# design.net
KiCad netlist of a schematic drawn in Altium Designer
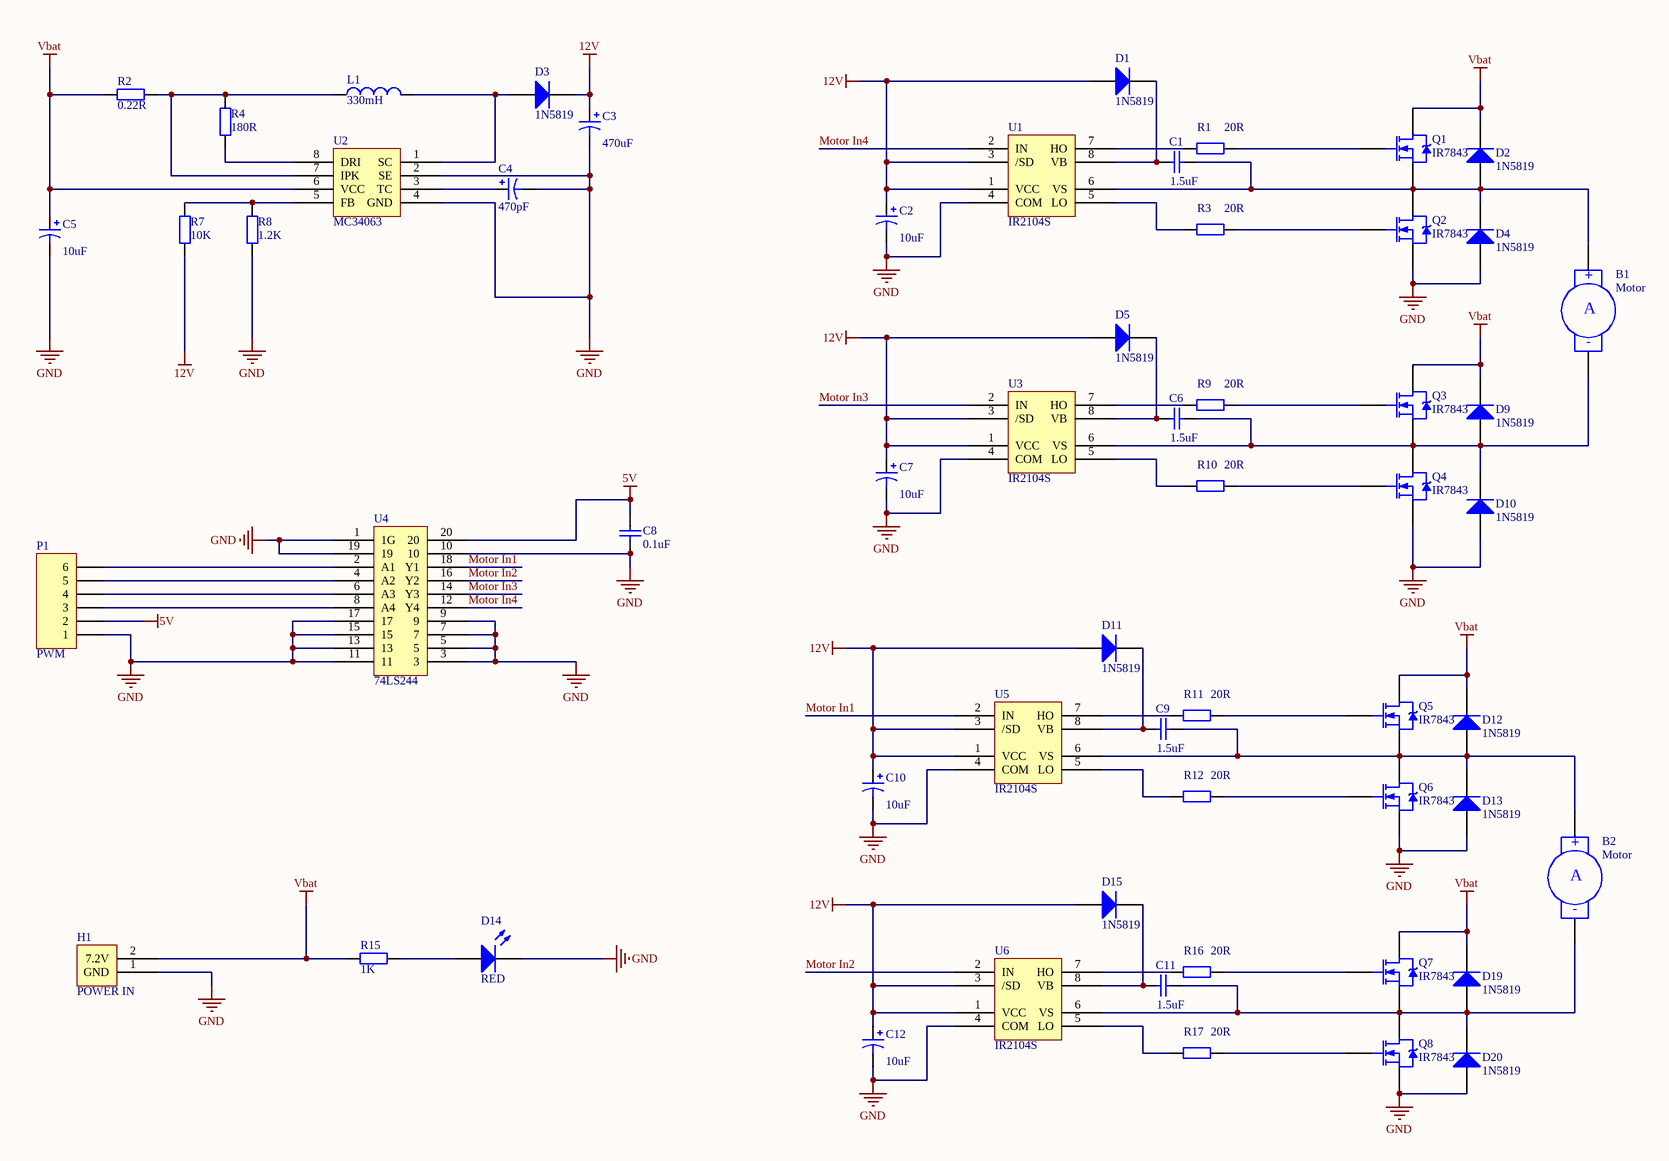
[diagram p0: 驱动原理图.SchDoc]

(export (version "E")
  (design (tool "Eeschema 10.0.6"))
  (components
    (comp (ref "B1")
      (value "Motor")
      (footprint "KF301-2P")
      (description "Servo Motor")
      (fields (field (name "PUBLISHER") "Altium Limited"))
      (libsource (lib "Miscellaneous Devices") (part "Motor Servo"))
    )
    (comp (ref "B2")
      (value "Motor")
      (footprint "KF301-2P")
      (description "Servo Motor")
      (fields (field (name "PUBLISHER") "Altium Limited"))
      (libsource (lib "Miscellaneous Devices") (part "Motor Servo"))
    )
    (comp (ref "C1")
      (value "1.5uF")
      (footprint "0805(2012)")
      (description "Capacitor")
      (fields (field (name "Comment") "Cap") (field (name "PUBLISHER") "Altium Limited"))
      (libsource (lib "Miscellaneous Devices") (part "Cap"))
    )
    (comp (ref "C2")
      (value "10uF")
      (footprint "SOD-323(0805)")
      (description "Polarized Capacitor (Radial)")
      (fields (field (name "Comment") "Cap Pol1") (field (name "PUBLISHER") "Altium Limited"))
      (libsource (lib "Miscellaneous Devices") (part "Cap Pol1"))
    )
    (comp (ref "C3")
      (value "470uF")
      (footprint "RB5-10.5")
      (description "Polarized Capacitor (Radial)")
      (fields (field (name "Comment") "Cap Pol1") (field (name "PUBLISHER") "Altium Limited"))
      (libsource (lib "Miscellaneous Devices") (part "Cap Pol1"))
    )
    (comp (ref "C4")
      (value "470pF")
      (footprint "SOD-323(0805)")
      (description "Polarized Capacitor (Radial)")
      (fields (field (name "Comment") "Cap Pol1") (field (name "PUBLISHER") "Altium Limited"))
      (libsource (lib "Miscellaneous Devices") (part "Cap Pol1"))
    )
    (comp (ref "C5")
      (value "10uF")
      (footprint "SOD-323(0805)")
      (description "Polarized Capacitor (Radial)")
      (fields (field (name "Comment") "Cap Pol1") (field (name "PUBLISHER") "Altium Limited"))
      (libsource (lib "Miscellaneous Devices") (part "Cap Pol1"))
    )
    (comp (ref "C6")
      (value "1.5uF")
      (footprint "0805(2012)")
      (description "Capacitor")
      (fields (field (name "Comment") "Cap") (field (name "PUBLISHER") "Altium Limited"))
      (libsource (lib "Miscellaneous Devices") (part "Cap"))
    )
    (comp (ref "C7")
      (value "10uF")
      (footprint "SOD-323(0805)")
      (description "Polarized Capacitor (Radial)")
      (fields (field (name "Comment") "Cap Pol1") (field (name "PUBLISHER") "Altium Limited"))
      (libsource (lib "Miscellaneous Devices") (part "Cap Pol1"))
    )
    (comp (ref "C8")
      (value "0.1uF")
      (footprint "0805(2012)")
      (description "Capacitor")
      (fields (field (name "Comment") "Cap") (field (name "PUBLISHER") "Altium Limited"))
      (libsource (lib "LY") (part "Cap"))
    )
    (comp (ref "C9")
      (value "1.5uF")
      (footprint "0805(2012)")
      (description "Capacitor")
      (fields (field (name "Comment") "Cap") (field (name "PUBLISHER") "Altium Limited"))
      (libsource (lib "Miscellaneous Devices") (part "Cap"))
    )
    (comp (ref "C10")
      (value "10uF")
      (footprint "SOD-323(0805)")
      (description "Polarized Capacitor (Radial)")
      (fields (field (name "Comment") "Cap Pol1") (field (name "PUBLISHER") "Altium Limited"))
      (libsource (lib "Miscellaneous Devices") (part "Cap Pol1"))
    )
    (comp (ref "C11")
      (value "1.5uF")
      (footprint "0805(2012)")
      (description "Capacitor")
      (fields (field (name "Comment") "Cap") (field (name "PUBLISHER") "Altium Limited"))
      (libsource (lib "Miscellaneous Devices") (part "Cap"))
    )
    (comp (ref "C12")
      (value "10uF")
      (footprint "SOD-323(0805)")
      (description "Polarized Capacitor (Radial)")
      (fields (field (name "Comment") "Cap Pol1") (field (name "PUBLISHER") "Altium Limited"))
      (libsource (lib "Miscellaneous Devices") (part "Cap Pol1"))
    )
    (comp (ref "D1")
      (value "1N5819")
      (footprint "0805(2012)")
      (description "Silicon Epitaxial Planar Diode for Various Detector, Modulator, Demodulator")
      (fields (field (name "PUBLISHER") "Altium Limited"))
      (libsource (lib "Renesas Diode") (part "1N4148"))
    )
    (comp (ref "D2")
      (value "1N5819")
      (footprint "0805(2012)")
      (description "Silicon Epitaxial Planar Diode for Various Detector, Modulator, Demodulator")
      (fields (field (name "PUBLISHER") "Altium Limited"))
      (libsource (lib "Renesas Diode") (part "1N4148"))
    )
    (comp (ref "D3")
      (value "1N5819")
      (footprint "0805(2012)")
      (description "Silicon Epitaxial Planar Diode for Various Detector, Modulator, Demodulator")
      (fields (field (name "PUBLISHER") "Altium Limited"))
      (libsource (lib "Renesas Diode") (part "1N4148"))
    )
    (comp (ref "D4")
      (value "1N5819")
      (footprint "0805(2012)")
      (description "Silicon Epitaxial Planar Diode for Various Detector, Modulator, Demodulator")
      (fields (field (name "PUBLISHER") "Altium Limited"))
      (libsource (lib "Renesas Diode") (part "1N4148"))
    )
    (comp (ref "D5")
      (value "1N5819")
      (footprint "0805(2012)")
      (description "Silicon Epitaxial Planar Diode for Various Detector, Modulator, Demodulator")
      (fields (field (name "PUBLISHER") "Altium Limited"))
      (libsource (lib "Renesas Diode") (part "1N4148"))
    )
    (comp (ref "D9")
      (value "1N5819")
      (footprint "0805(2012)")
      (description "Silicon Epitaxial Planar Diode for Various Detector, Modulator, Demodulator")
      (fields (field (name "PUBLISHER") "Altium Limited"))
      (libsource (lib "Renesas Diode") (part "1N4148"))
    )
    (comp (ref "D10")
      (value "1N5819")
      (footprint "0805(2012)")
      (description "Silicon Epitaxial Planar Diode for Various Detector, Modulator, Demodulator")
      (fields (field (name "PUBLISHER") "Altium Limited"))
      (libsource (lib "Renesas Diode") (part "1N4148"))
    )
    (comp (ref "D11")
      (value "1N5819")
      (footprint "0805(2012)")
      (description "Silicon Epitaxial Planar Diode for Various Detector, Modulator, Demodulator")
      (fields (field (name "PUBLISHER") "Altium Limited"))
      (libsource (lib "Renesas Diode") (part "1N4148"))
    )
    (comp (ref "D12")
      (value "1N5819")
      (footprint "0805(2012)")
      (description "Silicon Epitaxial Planar Diode for Various Detector, Modulator, Demodulator")
      (fields (field (name "PUBLISHER") "Altium Limited"))
      (libsource (lib "Renesas Diode") (part "1N4148"))
    )
    (comp (ref "D13")
      (value "1N5819")
      (footprint "0805(2012)")
      (description "Silicon Epitaxial Planar Diode for Various Detector, Modulator, Demodulator")
      (fields (field (name "PUBLISHER") "Altium Limited"))
      (libsource (lib "Renesas Diode") (part "1N4148"))
    )
    (comp (ref "D14")
      (value "RED")
      (footprint "0805LED")
      (description "Typical RED, GREEN, YELLOW, AMBER GaAs LED")
      (fields (field (name "PUBLISHER") "Altium Limited"))
      (libsource (lib "LY") (part "LED2"))
    )
    (comp (ref "D15")
      (value "1N5819")
      (footprint "0805(2012)")
      (description "Silicon Epitaxial Planar Diode for Various Detector, Modulator, Demodulator")
      (fields (field (name "PUBLISHER") "Altium Limited"))
      (libsource (lib "Renesas Diode") (part "1N4148"))
    )
    (comp (ref "D19")
      (value "1N5819")
      (footprint "0805(2012)")
      (description "Silicon Epitaxial Planar Diode for Various Detector, Modulator, Demodulator")
      (fields (field (name "PUBLISHER") "Altium Limited"))
      (libsource (lib "Renesas Diode") (part "1N4148"))
    )
    (comp (ref "D20")
      (value "1N5819")
      (footprint "0805(2012)")
      (description "Silicon Epitaxial Planar Diode for Various Detector, Modulator, Demodulator")
      (fields (field (name "PUBLISHER") "Altium Limited"))
      (libsource (lib "Renesas Diode") (part "1N4148"))
    )
    (comp (ref "H1")
      (value "POWER IN")
      (footprint "KF301-2P")
      (libsource (lib "MOS motor") (part "POWER IN"))
    )
    (comp (ref "L1")
      (value "330mH")
      (footprint "电感10*12")
      (description "Inductor")
      (fields (field (name "PUBLISHER") "Altium Limited"))
      (libsource (lib "Miscellaneous Devices") (part "Inductor"))
    )
    (comp (ref "P1")
      (value "PWM")
      (footprint "HDR1X6")
      (description "Header, 6-Pin")
      (fields (field (name "PUBLISHER") "Altium Limited"))
      (libsource (lib "Miscellaneous Connectors") (part "Header 6"))
    )
    (comp (ref "Q1")
      (value "IR7843")
      (footprint "LR7843")
      (description "N-Channel Power MOSFET")
      (fields (field (name "PUBLISHER") "Altium Limited"))
      (libsource (lib "PowerIn") (part "IR7843"))
    )
    (comp (ref "Q2")
      (value "IR7843")
      (footprint "LR7843")
      (description "N-Channel Power MOSFET")
      (fields (field (name "PUBLISHER") "Altium Limited"))
      (libsource (lib "PowerIn") (part "IR7843"))
    )
    (comp (ref "Q3")
      (value "IR7843")
      (footprint "LR7843")
      (description "N-Channel Power MOSFET")
      (fields (field (name "PUBLISHER") "Altium Limited"))
      (libsource (lib "PowerIn") (part "IR7843"))
    )
    (comp (ref "Q4")
      (value "IR7843")
      (footprint "LR7843")
      (description "N-Channel Power MOSFET")
      (fields (field (name "PUBLISHER") "Altium Limited"))
      (libsource (lib "PowerIn") (part "IR7843"))
    )
    (comp (ref "Q5")
      (value "IR7843")
      (footprint "LR7843")
      (description "N-Channel Power MOSFET")
      (fields (field (name "PUBLISHER") "Altium Limited"))
      (libsource (lib "PowerIn") (part "IR7843"))
    )
    (comp (ref "Q6")
      (value "IR7843")
      (footprint "LR7843")
      (description "N-Channel Power MOSFET")
      (fields (field (name "PUBLISHER") "Altium Limited"))
      (libsource (lib "PowerIn") (part "IR7843"))
    )
    (comp (ref "Q7")
      (value "IR7843")
      (footprint "LR7843")
      (description "N-Channel Power MOSFET")
      (fields (field (name "PUBLISHER") "Altium Limited"))
      (libsource (lib "PowerIn") (part "IR7843"))
    )
    (comp (ref "Q8")
      (value "IR7843")
      (footprint "LR7843")
      (description "N-Channel Power MOSFET")
      (fields (field (name "PUBLISHER") "Altium Limited"))
      (libsource (lib "PowerIn") (part "IR7843"))
    )
    (comp (ref "R1")
      (value "20R")
      (footprint "0805(2012)")
      (description "Resistor")
      (fields (field (name "Comment") "Res2") (field (name "PUBLISHER") "Altium Limited"))
      (libsource (lib "altium-import") (part "root_0_Res2_"))
    )
    (comp (ref "R2")
      (value "0.22R")
      (footprint "1206(3216)")
      (description "Resistor")
      (fields (field (name "Comment") "Res2") (field (name "PUBLISHER") "Altium Limited"))
      (libsource (lib "altium-import") (part "root_2_Res2_"))
    )
    (comp (ref "R3")
      (value "20R")
      (footprint "0805(2012)")
      (description "Resistor")
      (fields (field (name "Comment") "Res2") (field (name "PUBLISHER") "Altium Limited"))
      (libsource (lib "altium-import") (part "root_0_Res2_"))
    )
    (comp (ref "R4")
      (value "180R")
      (footprint "0805(2012)")
      (description "Resistor")
      (fields (field (name "Comment") "Res2") (field (name "PUBLISHER") "Altium Limited"))
      (libsource (lib "") (part "Res2_1"))
    )
    (comp (ref "R7")
      (value "10K")
      (footprint "0805(2012)")
      (description "Resistor")
      (fields (field (name "Comment") "Res2") (field (name "PUBLISHER") "Altium Limited"))
      (libsource (lib "") (part "Res2_1"))
    )
    (comp (ref "R8")
      (value "1.2K")
      (footprint "0805(2012)")
      (description "Resistor")
      (fields (field (name "Comment") "Res2") (field (name "PUBLISHER") "Altium Limited"))
      (libsource (lib "") (part "Res2_1"))
    )
    (comp (ref "R9")
      (value "20R")
      (footprint "0805(2012)")
      (description "Resistor")
      (fields (field (name "Comment") "Res2") (field (name "PUBLISHER") "Altium Limited"))
      (libsource (lib "altium-import") (part "root_0_Res2_"))
    )
    (comp (ref "R10")
      (value "20R")
      (footprint "0805(2012)")
      (description "Resistor")
      (fields (field (name "Comment") "Res2") (field (name "PUBLISHER") "Altium Limited"))
      (libsource (lib "altium-import") (part "root_0_Res2_"))
    )
    (comp (ref "R11")
      (value "20R")
      (footprint "0805(2012)")
      (description "Resistor")
      (fields (field (name "Comment") "Res2") (field (name "PUBLISHER") "Altium Limited"))
      (libsource (lib "altium-import") (part "root_0_Res2_"))
    )
    (comp (ref "R12")
      (value "20R")
      (footprint "0805(2012)")
      (description "Resistor")
      (fields (field (name "Comment") "Res2") (field (name "PUBLISHER") "Altium Limited"))
      (libsource (lib "altium-import") (part "root_0_Res2_"))
    )
    (comp (ref "R15")
      (value "1K")
      (footprint "0805(2012)")
      (description "Resistor")
      (fields (field (name "Comment") "Res2") (field (name "PUBLISHER") "Altium Limited"))
      (libsource (lib "LY") (part "Res2"))
    )
    (comp (ref "R16")
      (value "20R")
      (footprint "0805(2012)")
      (description "Resistor")
      (fields (field (name "Comment") "Res2") (field (name "PUBLISHER") "Altium Limited"))
      (libsource (lib "altium-import") (part "root_0_Res2_"))
    )
    (comp (ref "R17")
      (value "20R")
      (footprint "0805(2012)")
      (description "Resistor")
      (fields (field (name "Comment") "Res2") (field (name "PUBLISHER") "Altium Limited"))
      (libsource (lib "altium-import") (part "root_0_Res2_"))
    )
    (comp (ref "U1") (value "IR2104S") (footprint "IR2104S") (libsource (lib "LY") (part "IR2104S")))
    (comp (ref "U2") (value "MC34063") (footprint "MC34063") (libsource (lib "LY") (part "MC34063")))
    (comp (ref "U3") (value "IR2104S") (footprint "IR2104S") (libsource (lib "LY") (part "IR2104S")))
    (comp (ref "U4") (value "74LS244") (footprint "74ls244DA") (libsource (lib "LY") (part "74LS244")))
    (comp (ref "U5") (value "IR2104S") (footprint "IR2104S") (libsource (lib "LY") (part "IR2104S")))
    (comp (ref "U6") (value "IR2104S") (footprint "IR2104S") (libsource (lib "LY") (part "IR2104S")))
  )
  (nets
    (net (code "1") (name "/Motor In1") (class "Default")
      (node (ref "U4") (pin "18") (pinfunction "Y1_18") (pintype "passive"))
      (node (ref "U5") (pin "2") (pinfunction "IN_2") (pintype "passive"))
    )
    (net (code "2") (name "/Motor In2") (class "Default")
      (node (ref "U4") (pin "16") (pinfunction "Y2_16") (pintype "passive"))
      (node (ref "U6") (pin "2") (pinfunction "IN_2") (pintype "passive"))
    )
    (net (code "3") (name "/Motor In3") (class "Default")
      (node (ref "U3") (pin "2") (pinfunction "IN_2") (pintype "passive"))
      (node (ref "U4") (pin "14") (pinfunction "Y3_14") (pintype "passive"))
    )
    (net (code "4") (name "/Motor In4") (class "Default")
      (node (ref "U1") (pin "2") (pinfunction "IN_2") (pintype "passive"))
      (node (ref "U4") (pin "12") (pinfunction "Y4_12") (pintype "passive"))
    )
    (net (code "5") (name "5V") (class "Default")
      (node (ref "C8") (pin "2") (pinfunction "2_2") (pintype "passive"))
      (node (ref "P1") (pin "2") (pinfunction "2_2") (pintype "passive"))
      (node (ref "U4") (pin "20") (pinfunction "20_20") (pintype "passive"))
    )
    (net (code "6") (name "12V") (class "Default")
      (node (ref "C10") (pin "1") (pinfunction "1_1") (pintype "passive"))
      (node (ref "C12") (pin "1") (pinfunction "1_1") (pintype "passive"))
      (node (ref "C2") (pin "1") (pinfunction "1_1") (pintype "passive"))
      (node (ref "C3") (pin "1") (pinfunction "1_1") (pintype "passive"))
      (node (ref "C7") (pin "1") (pinfunction "1_1") (pintype "passive"))
      (node (ref "D1") (pin "2") (pinfunction "A_2") (pintype "passive"))
      (node (ref "D11") (pin "2") (pinfunction "A_2") (pintype "passive"))
      (node (ref "D15") (pin "2") (pinfunction "A_2") (pintype "passive"))
      (node (ref "D3") (pin "1") (pinfunction "K_1") (pintype "passive"))
      (node (ref "D5") (pin "2") (pinfunction "A_2") (pintype "passive"))
      (node (ref "R7") (pin "1") (pinfunction "1_1") (pintype "passive"))
      (node (ref "U1") (pin "1") (pinfunction "VCC_1") (pintype "passive"))
      (node (ref "U1") (pin "3") (pinfunction "/SD_3") (pintype "passive"))
      (node (ref "U3") (pin "1") (pinfunction "VCC_1") (pintype "passive"))
      (node (ref "U3") (pin "3") (pinfunction "/SD_3") (pintype "passive"))
      (node (ref "U5") (pin "1") (pinfunction "VCC_1") (pintype "passive"))
      (node (ref "U5") (pin "3") (pinfunction "/SD_3") (pintype "passive"))
      (node (ref "U6") (pin "1") (pinfunction "VCC_1") (pintype "passive"))
      (node (ref "U6") (pin "3") (pinfunction "/SD_3") (pintype "passive"))
    )
    (net (code "7") (name "GND") (class "Default")
      (node (ref "C10") (pin "2") (pinfunction "2_2") (pintype "passive"))
      (node (ref "C12") (pin "2") (pinfunction "2_2") (pintype "passive"))
      (node (ref "C2") (pin "2") (pinfunction "2_2") (pintype "passive"))
      (node (ref "C3") (pin "2") (pinfunction "2_2") (pintype "passive"))
      (node (ref "C4") (pin "2") (pinfunction "2_2") (pintype "passive"))
      (node (ref "C5") (pin "2") (pinfunction "2_2") (pintype "passive"))
      (node (ref "C7") (pin "2") (pinfunction "2_2") (pintype "passive"))
      (node (ref "C8") (pin "1") (pinfunction "1_1") (pintype "passive"))
      (node (ref "D10") (pin "2") (pinfunction "A_2") (pintype "passive"))
      (node (ref "D13") (pin "2") (pinfunction "A_2") (pintype "passive"))
      (node (ref "D14") (pin "2") (pinfunction "K_2") (pintype "passive"))
      (node (ref "D20") (pin "2") (pinfunction "A_2") (pintype "passive"))
      (node (ref "D4") (pin "2") (pinfunction "A_2") (pintype "passive"))
      (node (ref "H1") (pin "1") (pinfunction "GND_1") (pintype "passive"))
      (node (ref "P1") (pin "1") (pinfunction "1_1") (pintype "passive"))
      (node (ref "Q2") (pin "3") (pinfunction "S_3") (pintype "passive"))
      (node (ref "Q4") (pin "3") (pinfunction "S_3") (pintype "passive"))
      (node (ref "Q6") (pin "3") (pinfunction "S_3") (pintype "passive"))
      (node (ref "Q8") (pin "3") (pinfunction "S_3") (pintype "passive"))
      (node (ref "R8") (pin "1") (pinfunction "1_1") (pintype "passive"))
      (node (ref "U1") (pin "4") (pinfunction "COM_4") (pintype "passive"))
      (node (ref "U2") (pin "2") (pinfunction "SE_2") (pintype "passive"))
      (node (ref "U2") (pin "4") (pinfunction "GND_4") (pintype "passive"))
      (node (ref "U3") (pin "4") (pinfunction "COM_4") (pintype "passive"))
      (node (ref "U4") (pin "1") (pinfunction "1G_1") (pintype "passive"))
      (node (ref "U4") (pin "10") (pinfunction "10_10") (pintype "passive"))
      (node (ref "U4") (pin "11") (pinfunction "11_11") (pintype "passive"))
      (node (ref "U4") (pin "13") (pinfunction "13_13") (pintype "passive"))
      (node (ref "U4") (pin "15") (pinfunction "15_15") (pintype "passive"))
      (node (ref "U4") (pin "17") (pinfunction "17_17") (pintype "passive"))
      (node (ref "U4") (pin "19") (pinfunction "19_19") (pintype "passive"))
      (node (ref "U4") (pin "3") (pinfunction "3_3") (pintype "passive"))
      (node (ref "U4") (pin "5") (pinfunction "5_5") (pintype "passive"))
      (node (ref "U4") (pin "7") (pinfunction "7_7") (pintype "passive"))
      (node (ref "U4") (pin "9") (pinfunction "9_9") (pintype "passive"))
      (node (ref "U5") (pin "4") (pinfunction "COM_4") (pintype "passive"))
      (node (ref "U6") (pin "4") (pinfunction "COM_4") (pintype "passive"))
    )
    (net (code "8") (name "Net-(B1-+)") (class "Default")
      (node (ref "B1") (pin "1") (pinfunction "+_1") (pintype "passive"))
      (node (ref "C1") (pin "2") (pinfunction "2_2") (pintype "passive"))
      (node (ref "D2") (pin "2") (pinfunction "A_2") (pintype "passive"))
      (node (ref "D4") (pin "1") (pinfunction "K_1") (pintype "passive"))
      (node (ref "Q1") (pin "3") (pinfunction "S_3") (pintype "passive"))
      (node (ref "Q2") (pin "2") (pinfunction "D_2") (pintype "passive"))
      (node (ref "U1") (pin "6") (pinfunction "VS_6") (pintype "passive"))
    )
    (net (code "9") (name "Net-(B1--)") (class "Default")
      (node (ref "B1") (pin "2") (pinfunction "-_2") (pintype "passive"))
      (node (ref "C6") (pin "2") (pinfunction "2_2") (pintype "passive"))
      (node (ref "D10") (pin "1") (pinfunction "K_1") (pintype "passive"))
      (node (ref "D9") (pin "2") (pinfunction "A_2") (pintype "passive"))
      (node (ref "Q3") (pin "3") (pinfunction "S_3") (pintype "passive"))
      (node (ref "Q4") (pin "2") (pinfunction "D_2") (pintype "passive"))
      (node (ref "U3") (pin "6") (pinfunction "VS_6") (pintype "passive"))
    )
    (net (code "10") (name "Net-(B2-+)") (class "Default")
      (node (ref "B2") (pin "1") (pinfunction "+_1") (pintype "passive"))
      (node (ref "C9") (pin "2") (pinfunction "2_2") (pintype "passive"))
      (node (ref "D12") (pin "2") (pinfunction "A_2") (pintype "passive"))
      (node (ref "D13") (pin "1") (pinfunction "K_1") (pintype "passive"))
      (node (ref "Q5") (pin "3") (pinfunction "S_3") (pintype "passive"))
      (node (ref "Q6") (pin "2") (pinfunction "D_2") (pintype "passive"))
      (node (ref "U5") (pin "6") (pinfunction "VS_6") (pintype "passive"))
    )
    (net (code "11") (name "Net-(B2--)") (class "Default")
      (node (ref "B2") (pin "2") (pinfunction "-_2") (pintype "passive"))
      (node (ref "C11") (pin "2") (pinfunction "2_2") (pintype "passive"))
      (node (ref "D19") (pin "2") (pinfunction "A_2") (pintype "passive"))
      (node (ref "D20") (pin "1") (pinfunction "K_1") (pintype "passive"))
      (node (ref "Q7") (pin "3") (pinfunction "S_3") (pintype "passive"))
      (node (ref "Q8") (pin "2") (pinfunction "D_2") (pintype "passive"))
      (node (ref "U6") (pin "6") (pinfunction "VS_6") (pintype "passive"))
    )
    (net (code "12") (name "Net-(D1-K)") (class "Default")
      (node (ref "C1") (pin "1") (pinfunction "1_1") (pintype "passive"))
      (node (ref "D1") (pin "1") (pinfunction "K_1") (pintype "passive"))
      (node (ref "U1") (pin "8") (pinfunction "VB_8") (pintype "passive"))
    )
    (net (code "13") (name "Net-(D3-A)") (class "Default")
      (node (ref "D3") (pin "2") (pinfunction "A_2") (pintype "passive"))
      (node (ref "L1") (pin "2") (pinfunction "2_2") (pintype "passive"))
      (node (ref "U2") (pin "1") (pinfunction "SC_1") (pintype "passive"))
    )
    (net (code "14") (name "Net-(D5-K)") (class "Default")
      (node (ref "C6") (pin "1") (pinfunction "1_1") (pintype "passive"))
      (node (ref "D5") (pin "1") (pinfunction "K_1") (pintype "passive"))
      (node (ref "U3") (pin "8") (pinfunction "VB_8") (pintype "passive"))
    )
    (net (code "15") (name "Net-(D11-K)") (class "Default")
      (node (ref "C9") (pin "1") (pinfunction "1_1") (pintype "passive"))
      (node (ref "D11") (pin "1") (pinfunction "K_1") (pintype "passive"))
      (node (ref "U5") (pin "8") (pinfunction "VB_8") (pintype "passive"))
    )
    (net (code "16") (name "Net-(D14-A)") (class "Default")
      (node (ref "D14") (pin "1") (pinfunction "A_1") (pintype "passive"))
      (node (ref "R15") (pin "2") (pinfunction "2_2") (pintype "passive"))
    )
    (net (code "17") (name "Net-(D15-K)") (class "Default")
      (node (ref "C11") (pin "1") (pinfunction "1_1") (pintype "passive"))
      (node (ref "D15") (pin "1") (pinfunction "K_1") (pintype "passive"))
      (node (ref "U6") (pin "8") (pinfunction "VB_8") (pintype "passive"))
    )
    (net (code "18") (name "Net-(Q1-G)") (class "Default")
      (node (ref "Q1") (pin "1") (pinfunction "G_1") (pintype "passive"))
      (node (ref "R1") (pin "2") (pinfunction "2_2") (pintype "passive"))
    )
    (net (code "19") (name "Net-(Q2-G)") (class "Default")
      (node (ref "Q2") (pin "1") (pinfunction "G_1") (pintype "passive"))
      (node (ref "R3") (pin "2") (pinfunction "2_2") (pintype "passive"))
    )
    (net (code "20") (name "Net-(Q3-G)") (class "Default")
      (node (ref "Q3") (pin "1") (pinfunction "G_1") (pintype "passive"))
      (node (ref "R9") (pin "2") (pinfunction "2_2") (pintype "passive"))
    )
    (net (code "21") (name "Net-(Q4-G)") (class "Default")
      (node (ref "Q4") (pin "1") (pinfunction "G_1") (pintype "passive"))
      (node (ref "R10") (pin "2") (pinfunction "2_2") (pintype "passive"))
    )
    (net (code "22") (name "Net-(Q5-G)") (class "Default")
      (node (ref "Q5") (pin "1") (pinfunction "G_1") (pintype "passive"))
      (node (ref "R11") (pin "2") (pinfunction "2_2") (pintype "passive"))
    )
    (net (code "23") (name "Net-(Q6-G)") (class "Default")
      (node (ref "Q6") (pin "1") (pinfunction "G_1") (pintype "passive"))
      (node (ref "R12") (pin "2") (pinfunction "2_2") (pintype "passive"))
    )
    (net (code "24") (name "Net-(Q7-G)") (class "Default")
      (node (ref "Q7") (pin "1") (pinfunction "G_1") (pintype "passive"))
      (node (ref "R16") (pin "2") (pinfunction "2_2") (pintype "passive"))
    )
    (net (code "25") (name "Net-(Q8-G)") (class "Default")
      (node (ref "Q8") (pin "1") (pinfunction "G_1") (pintype "passive"))
      (node (ref "R17") (pin "2") (pinfunction "2_2") (pintype "passive"))
    )
    (net (code "26") (name "Net-(U1-HO)") (class "Default")
      (node (ref "R1") (pin "1") (pinfunction "1_1") (pintype "passive"))
      (node (ref "U1") (pin "7") (pinfunction "HO_7") (pintype "passive"))
    )
    (net (code "27") (name "Net-(U1-LO)") (class "Default")
      (node (ref "R3") (pin "1") (pinfunction "1_1") (pintype "passive"))
      (node (ref "U1") (pin "5") (pinfunction "LO_5") (pintype "passive"))
    )
    (net (code "28") (name "Net-(U2-DRI)") (class "Default")
      (node (ref "R4") (pin "1") (pinfunction "1_1") (pintype "passive"))
      (node (ref "U2") (pin "8") (pinfunction "DRI_8") (pintype "passive"))
    )
    (net (code "29") (name "Net-(U2-FB)") (class "Default")
      (node (ref "R7") (pin "2") (pinfunction "2_2") (pintype "passive"))
      (node (ref "R8") (pin "2") (pinfunction "2_2") (pintype "passive"))
      (node (ref "U2") (pin "5") (pinfunction "FB_5") (pintype "passive"))
    )
    (net (code "30") (name "Net-(U2-IPK)") (class "Default")
      (node (ref "L1") (pin "1") (pinfunction "1_1") (pintype "passive"))
      (node (ref "R2") (pin "1") (pinfunction "1_1") (pintype "passive"))
      (node (ref "R4") (pin "2") (pinfunction "2_2") (pintype "passive"))
      (node (ref "U2") (pin "7") (pinfunction "IPK_7") (pintype "passive"))
    )
    (net (code "31") (name "Net-(U2-TC)") (class "Default")
      (node (ref "C4") (pin "1") (pinfunction "1_1") (pintype "passive"))
      (node (ref "U2") (pin "3") (pinfunction "TC_3") (pintype "passive"))
    )
    (net (code "32") (name "Net-(U3-HO)") (class "Default")
      (node (ref "R9") (pin "1") (pinfunction "1_1") (pintype "passive"))
      (node (ref "U3") (pin "7") (pinfunction "HO_7") (pintype "passive"))
    )
    (net (code "33") (name "Net-(U3-LO)") (class "Default")
      (node (ref "R10") (pin "1") (pinfunction "1_1") (pintype "passive"))
      (node (ref "U3") (pin "5") (pinfunction "LO_5") (pintype "passive"))
    )
    (net (code "34") (name "Net-(U4-A1)") (class "Default")
      (node (ref "P1") (pin "6") (pinfunction "6_6") (pintype "passive"))
      (node (ref "U4") (pin "2") (pinfunction "A1_2") (pintype "passive"))
    )
    (net (code "35") (name "Net-(U4-A2)") (class "Default")
      (node (ref "P1") (pin "5") (pinfunction "5_5") (pintype "passive"))
      (node (ref "U4") (pin "4") (pinfunction "A2_4") (pintype "passive"))
    )
    (net (code "36") (name "Net-(U4-A3)") (class "Default")
      (node (ref "P1") (pin "4") (pinfunction "4_4") (pintype "passive"))
      (node (ref "U4") (pin "6") (pinfunction "A3_6") (pintype "passive"))
    )
    (net (code "37") (name "Net-(U4-A4)") (class "Default")
      (node (ref "P1") (pin "3") (pinfunction "3_3") (pintype "passive"))
      (node (ref "U4") (pin "8") (pinfunction "A4_8") (pintype "passive"))
    )
    (net (code "38") (name "Net-(U5-HO)") (class "Default")
      (node (ref "R11") (pin "1") (pinfunction "1_1") (pintype "passive"))
      (node (ref "U5") (pin "7") (pinfunction "HO_7") (pintype "passive"))
    )
    (net (code "39") (name "Net-(U5-LO)") (class "Default")
      (node (ref "R12") (pin "1") (pinfunction "1_1") (pintype "passive"))
      (node (ref "U5") (pin "5") (pinfunction "LO_5") (pintype "passive"))
    )
    (net (code "40") (name "Net-(U6-HO)") (class "Default")
      (node (ref "R16") (pin "1") (pinfunction "1_1") (pintype "passive"))
      (node (ref "U6") (pin "7") (pinfunction "HO_7") (pintype "passive"))
    )
    (net (code "41") (name "Net-(U6-LO)") (class "Default")
      (node (ref "R17") (pin "1") (pinfunction "1_1") (pintype "passive"))
      (node (ref "U6") (pin "5") (pinfunction "LO_5") (pintype "passive"))
    )
    (net (code "42") (name "Vbat") (class "Default")
      (node (ref "C5") (pin "1") (pinfunction "1_1") (pintype "passive"))
      (node (ref "D12") (pin "1") (pinfunction "K_1") (pintype "passive"))
      (node (ref "D19") (pin "1") (pinfunction "K_1") (pintype "passive"))
      (node (ref "D2") (pin "1") (pinfunction "K_1") (pintype "passive"))
      (node (ref "D9") (pin "1") (pinfunction "K_1") (pintype "passive"))
      (node (ref "H1") (pin "2") (pinfunction "7.2V_2") (pintype "passive"))
      (node (ref "Q1") (pin "2") (pinfunction "D_2") (pintype "passive"))
      (node (ref "Q3") (pin "2") (pinfunction "D_2") (pintype "passive"))
      (node (ref "Q5") (pin "2") (pinfunction "D_2") (pintype "passive"))
      (node (ref "Q7") (pin "2") (pinfunction "D_2") (pintype "passive"))
      (node (ref "R15") (pin "1") (pinfunction "1_1") (pintype "passive"))
      (node (ref "R2") (pin "2") (pinfunction "2_2") (pintype "passive"))
      (node (ref "U2") (pin "6") (pinfunction "VCC_6") (pintype "passive"))
    )
  )
)
